# OP3_BUTTON_EasyEDA.net
KiCad netlist of a schematic drawn in EasyEDA
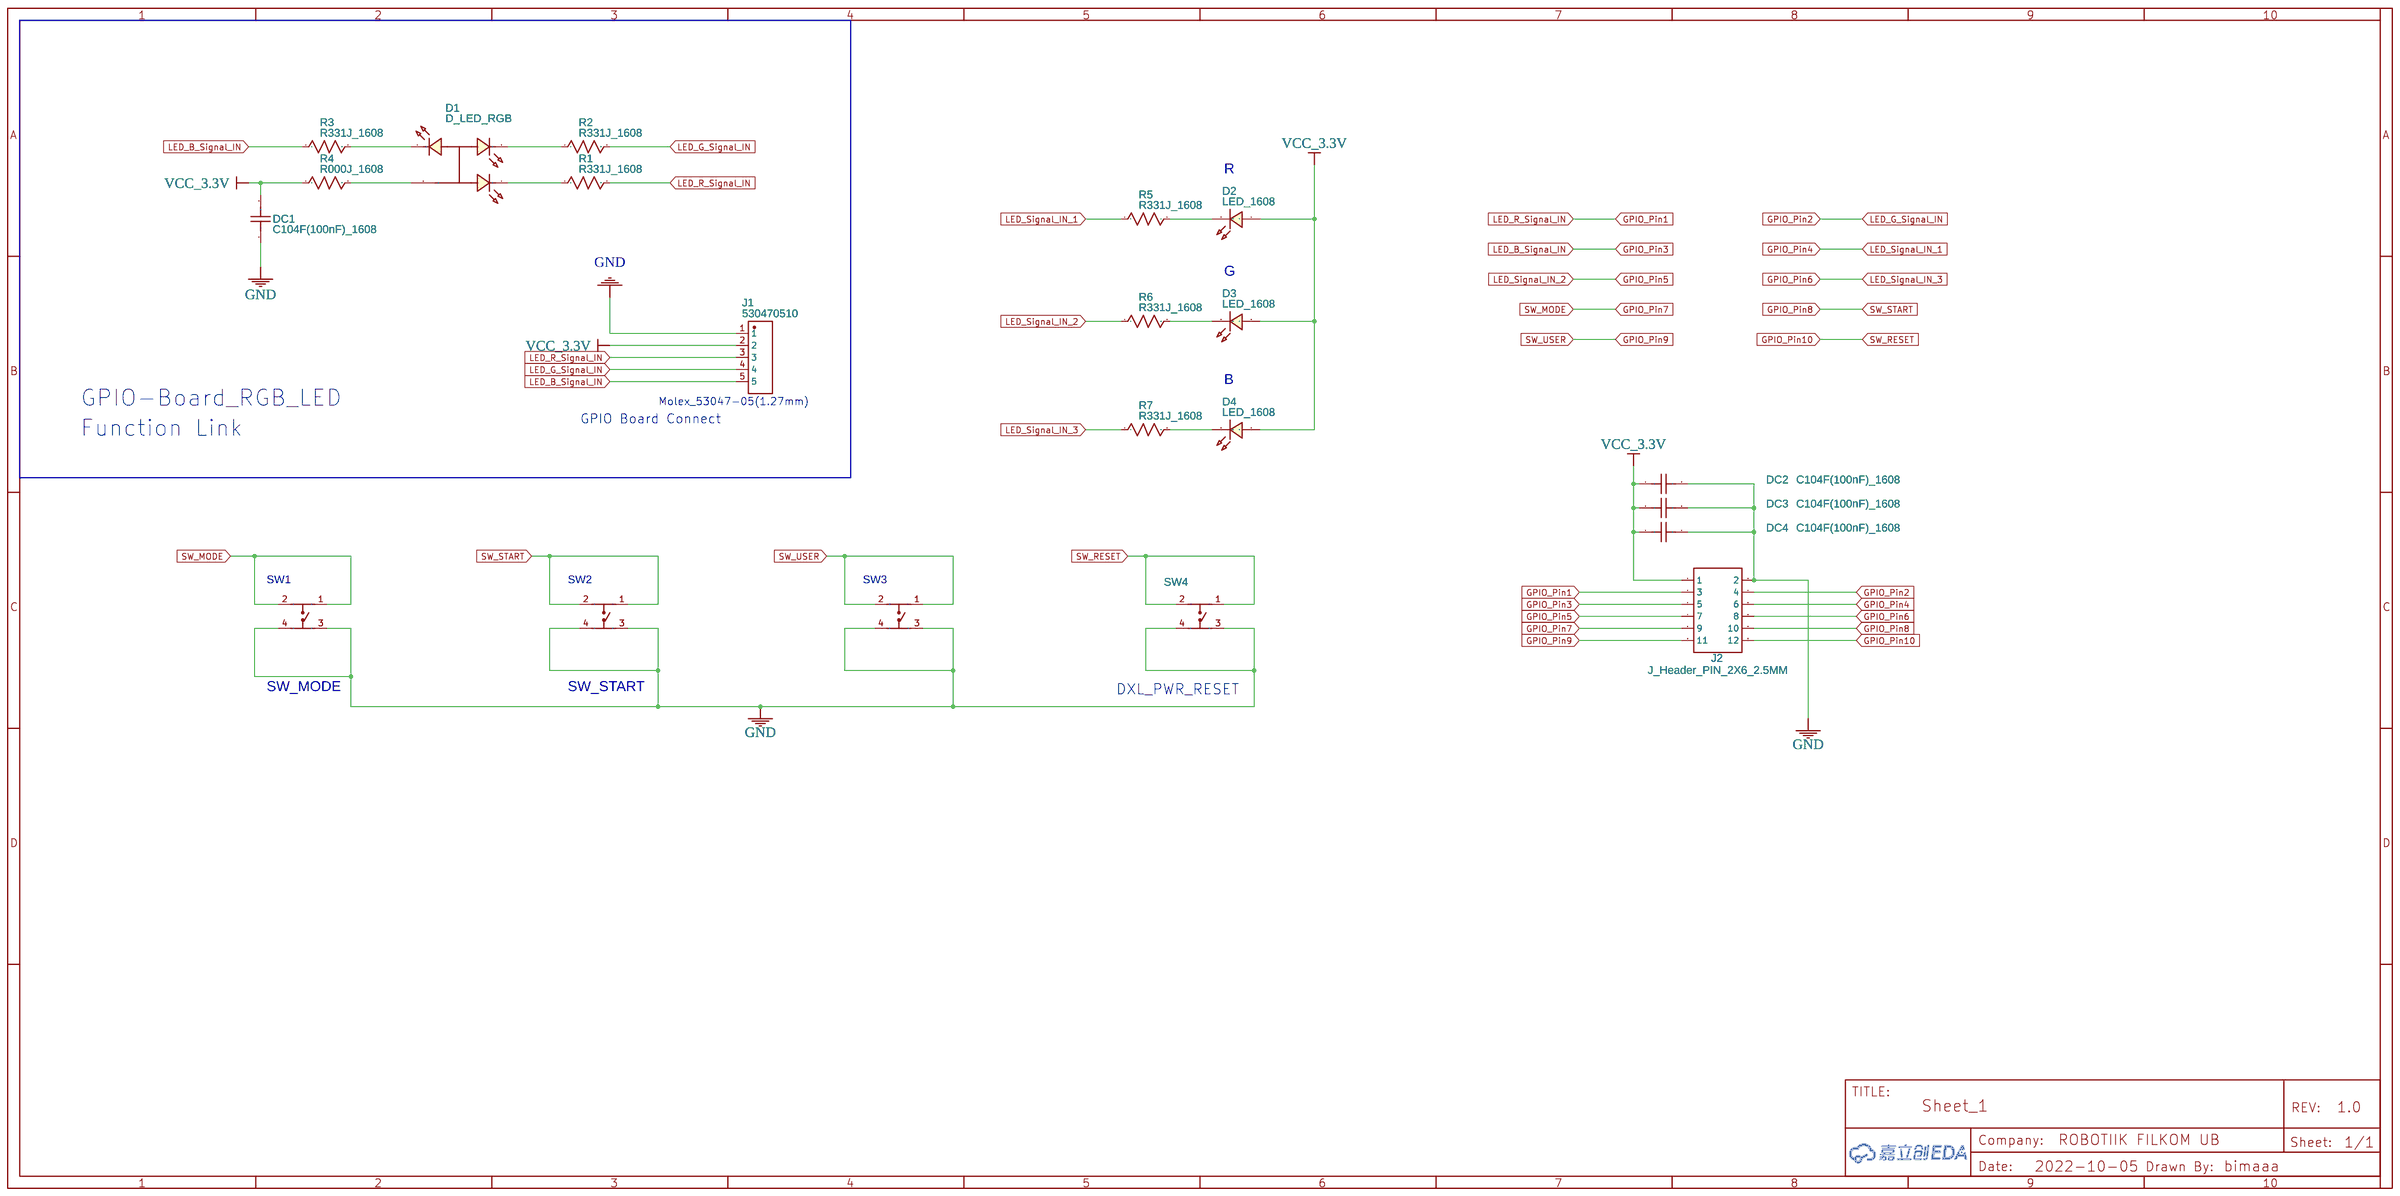
[diagram p0: schematic sheet]

(export (version "E")
  (design (tool "Eeschema 10.0.6"))
  (components
    (comp (ref "D1")
      (value "D_LED_RGB")
      (fields
        (field (name "BOM_Manufacturer Part") "YXD-1204RGB-C")
        (field (name "BOM_Supplier Part") "C9900001072")
      )
      (libsource (lib "") (part "YXD-1204RGB-C"))
    )
    (comp (ref "D2")
      (value "LED_1608")
      (fields
        (field (name "BOM_Manufacturer Part") "19-217/R6C-AL1M2VY/3T")
        (field (name "BOM_Supplier Part") "C72044")
      )
      (libsource (lib "") (part "LED-0603_R"))
    )
    (comp (ref "D3")
      (value "LED_1608")
      (fields
        (field (name "BOM_Manufacturer Part") "19-217/R6C-AL1M2VY/3T")
        (field (name "BOM_Supplier Part") "C72044")
      )
      (libsource (lib "") (part "LED-0603_R"))
    )
    (comp (ref "D4")
      (value "LED_1608")
      (fields
        (field (name "BOM_Manufacturer Part") "19-217/R6C-AL1M2VY/3T")
        (field (name "BOM_Supplier Part") "C72044")
      )
      (libsource (lib "") (part "LED-0603_R"))
    )
    (comp (ref "DC1") (value "C104F(100nF)_1608") (libsource (lib "") (part "C_0603_US_1")))
    (comp (ref "DC2") (value "C104F(100nF)_1608") (libsource (lib "") (part "C_0603_US")))
    (comp (ref "DC3") (value "C104F(100nF)_1608") (libsource (lib "") (part "C_0603_US")))
    (comp (ref "DC4") (value "C104F(100nF)_1608") (libsource (lib "") (part "C_0603_US")))
    (comp (ref "J1")
      (value "530470510")
      (fields (field (name "BOM_Supplier Part") "C471412"))
      (libsource (lib "") (part "530470510"))
    )
    (comp (ref "J2")
      (value "J_Header_PIN_2X6_2.5MM")
      (fields (field (name "BOM_Supplier Part") "C66689"))
      (libsource (lib "") (part "Header-Male-2.54_2x6"))
    )
    (comp (ref "R1") (value "R331J_1608") (libsource (lib "") (part "R_0603_US")))
    (comp (ref "R2") (value "R331J_1608") (libsource (lib "") (part "R_0603_US")))
    (comp (ref "R3") (value "R331J_1608") (libsource (lib "") (part "R_0603_US")))
    (comp (ref "R4") (value "R000J_1608") (libsource (lib "") (part "R_0603_US")))
    (comp (ref "R5") (value "R331J_1608") (libsource (lib "") (part "R_0603_US")))
    (comp (ref "R6") (value "R331J_1608") (libsource (lib "") (part "R_0603_US")))
    (comp (ref "R7") (value "R331J_1608") (libsource (lib "") (part "R_0603_US")))
    (comp (ref "SW3")
      (value "SMD Tactile Switch6*6*6mm")
      (fields (field (name "Manufacturer Part") "贴片轻触开关6*6*6mm"))
      (libsource (lib "") (part "SMD Tactile Switch6*6*6mm"))
    )
    (comp (ref "SW4")
      (value "SMD Tactile Switch6*6*6mm")
      (fields (field (name "Manufacturer Part") "贴片轻触开关6*6*6mm"))
      (libsource (lib "") (part "SMD Tactile Switch6*6*6mm"))
    )
    (comp (ref "SW5")
      (value "SMD Tactile Switch6*6*6mm")
      (fields (field (name "Manufacturer Part") "贴片轻触开关6*6*6mm"))
      (libsource (lib "") (part "SMD Tactile Switch6*6*6mm"))
    )
    (comp (ref "SW6")
      (value "SMD Tactile Switch6*6*6mm")
      (fields (field (name "Manufacturer Part") "贴片轻触开关6*6*6mm"))
      (libsource (lib "") (part "SMD Tactile Switch6*6*6mm"))
    )
  )
  (nets
    (net (code "1") (name "GND") (class "Default")
      (node (ref "DC1") (pin "1") (pinfunction "1_1") (pintype "unspecified"))
      (node (ref "DC2") (pin "2") (pinfunction "2_2") (pintype "unspecified"))
      (node (ref "DC3") (pin "2") (pinfunction "2_2") (pintype "unspecified"))
      (node (ref "DC4") (pin "2") (pinfunction "2_2") (pintype "unspecified"))
      (node (ref "J1") (pin "1") (pinfunction "1_1") (pintype "unspecified"))
      (node (ref "J2") (pin "2") (pinfunction "2_2") (pintype "input"))
      (node (ref "SW3") (pin "3") (pinfunction "3_3") (pintype "unspecified"))
      (node (ref "SW3") (pin "4") (pinfunction "4_4") (pintype "unspecified"))
      (node (ref "SW4") (pin "3") (pinfunction "3_3") (pintype "unspecified"))
      (node (ref "SW4") (pin "4") (pinfunction "4_4") (pintype "unspecified"))
      (node (ref "SW5") (pin "3") (pinfunction "3_3") (pintype "unspecified"))
      (node (ref "SW5") (pin "4") (pinfunction "4_4") (pintype "unspecified"))
      (node (ref "SW6") (pin "3") (pinfunction "3_3") (pintype "unspecified"))
      (node (ref "SW6") (pin "4") (pinfunction "4_4") (pintype "unspecified"))
    )
    (net (code "2") (name "GPIO_Pin1") (class "Default")
      (node (ref "J1") (pin "3") (pinfunction "3_3") (pintype "unspecified"))
      (node (ref "J2") (pin "3") (pinfunction "3_3") (pintype "input"))
      (node (ref "R1") (pin "2") (pinfunction "2_2") (pintype "unspecified"))
    )
    (net (code "3") (name "GPIO_Pin2") (class "Default")
      (node (ref "J1") (pin "4") (pinfunction "4_4") (pintype "unspecified"))
      (node (ref "J2") (pin "4") (pinfunction "4_4") (pintype "input"))
      (node (ref "R2") (pin "2") (pinfunction "2_2") (pintype "unspecified"))
    )
    (net (code "4") (name "GPIO_Pin3") (class "Default")
      (node (ref "J1") (pin "5") (pinfunction "5_5") (pintype "unspecified"))
      (node (ref "J2") (pin "5") (pinfunction "5_5") (pintype "input"))
      (node (ref "R3") (pin "1") (pinfunction "1_1") (pintype "unspecified"))
    )
    (net (code "5") (name "GPIO_Pin4") (class "Default")
      (node (ref "J2") (pin "6") (pinfunction "6_6") (pintype "input"))
      (node (ref "R5") (pin "1") (pinfunction "1_1") (pintype "unspecified"))
    )
    (net (code "6") (name "GPIO_Pin5") (class "Default")
      (node (ref "J2") (pin "7") (pinfunction "7_7") (pintype "input"))
      (node (ref "R6") (pin "1") (pinfunction "1_1") (pintype "unspecified"))
    )
    (net (code "7") (name "GPIO_Pin6") (class "Default")
      (node (ref "J2") (pin "8") (pinfunction "8_8") (pintype "input"))
      (node (ref "R7") (pin "1") (pinfunction "1_1") (pintype "unspecified"))
    )
    (net (code "8") (name "GPIO_Pin7") (class "Default")
      (node (ref "J2") (pin "9") (pinfunction "9_9") (pintype "input"))
      (node (ref "SW3") (pin "1") (pinfunction "1_1") (pintype "unspecified"))
      (node (ref "SW3") (pin "2") (pinfunction "2_2") (pintype "unspecified"))
    )
    (net (code "9") (name "GPIO_Pin8") (class "Default")
      (node (ref "J2") (pin "10") (pinfunction "10_10") (pintype "input"))
      (node (ref "SW5") (pin "1") (pinfunction "1_1") (pintype "unspecified"))
      (node (ref "SW5") (pin "2") (pinfunction "2_2") (pintype "unspecified"))
    )
    (net (code "10") (name "GPIO_Pin9") (class "Default")
      (node (ref "J2") (pin "11") (pinfunction "11_11") (pintype "input"))
      (node (ref "SW6") (pin "1") (pinfunction "1_1") (pintype "unspecified"))
      (node (ref "SW6") (pin "2") (pinfunction "2_2") (pintype "unspecified"))
    )
    (net (code "11") (name "GPIO_Pin10") (class "Default")
      (node (ref "J2") (pin "12") (pinfunction "12_12") (pintype "input"))
      (node (ref "SW4") (pin "1") (pinfunction "1_1") (pintype "unspecified"))
      (node (ref "SW4") (pin "2") (pinfunction "2_2") (pintype "unspecified"))
    )
    (net (code "12") (name "Net-(D1-K-Pad1)") (class "Default")
      (node (ref "D1") (pin "1") (pinfunction "K_1") (pintype "unspecified"))
      (node (ref "R3") (pin "2") (pinfunction "2_2") (pintype "unspecified"))
    )
    (net (code "13") (name "Net-(D1-K-Pad2)") (class "Default")
      (node (ref "D1") (pin "2") (pinfunction "K_2") (pintype "unspecified"))
      (node (ref "R2") (pin "1") (pinfunction "1_1") (pintype "unspecified"))
    )
    (net (code "14") (name "Net-(D1-K-Pad4)") (class "Default")
      (node (ref "D1") (pin "4") (pinfunction "K_4") (pintype "unspecified"))
      (node (ref "R1") (pin "1") (pinfunction "1_1") (pintype "unspecified"))
    )
    (net (code "15") (name "Net-(D1-Pad3)") (class "Default")
      (node (ref "D1") (pin "3") (pinfunction "3_3") (pintype "unspecified"))
      (node (ref "R4") (pin "2") (pinfunction "2_2") (pintype "unspecified"))
    )
    (net (code "16") (name "Net-(D2-Pad2)") (class "Default")
      (node (ref "D2") (pin "2") (pinfunction "2_2") (pintype "unspecified"))
      (node (ref "R5") (pin "2") (pinfunction "2_2") (pintype "unspecified"))
    )
    (net (code "17") (name "Net-(D3-Pad2)") (class "Default")
      (node (ref "D3") (pin "2") (pinfunction "2_2") (pintype "unspecified"))
      (node (ref "R6") (pin "2") (pinfunction "2_2") (pintype "unspecified"))
    )
    (net (code "18") (name "Net-(D4-Pad2)") (class "Default")
      (node (ref "D4") (pin "2") (pinfunction "2_2") (pintype "unspecified"))
      (node (ref "R7") (pin "2") (pinfunction "2_2") (pintype "unspecified"))
    )
    (net (code "19") (name "VCC_3.3V") (class "Default")
      (node (ref "D2") (pin "1") (pinfunction "1_1") (pintype "unspecified"))
      (node (ref "D3") (pin "1") (pinfunction "1_1") (pintype "unspecified"))
      (node (ref "D4") (pin "1") (pinfunction "1_1") (pintype "unspecified"))
      (node (ref "DC1") (pin "2") (pinfunction "2_2") (pintype "unspecified"))
      (node (ref "DC2") (pin "1") (pinfunction "1_1") (pintype "unspecified"))
      (node (ref "DC3") (pin "1") (pinfunction "1_1") (pintype "unspecified"))
      (node (ref "DC4") (pin "1") (pinfunction "1_1") (pintype "unspecified"))
      (node (ref "J1") (pin "2") (pinfunction "2_2") (pintype "unspecified"))
      (node (ref "J2") (pin "1") (pinfunction "1_1") (pintype "input"))
      (node (ref "R4") (pin "1") (pinfunction "1_1") (pintype "unspecified"))
    )
  )
)
